# Machnguon.net
KiCad netlist of a schematic drawn in Altium Designer
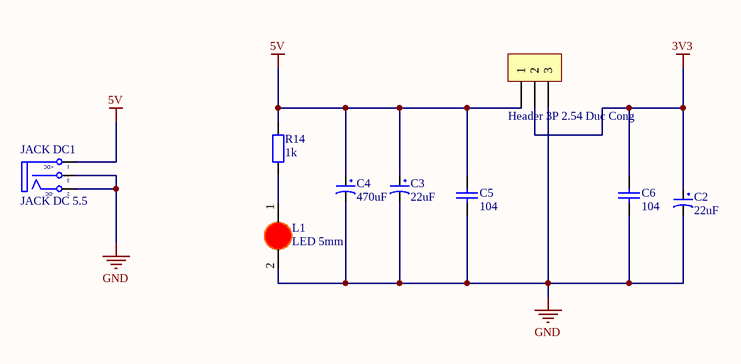
[diagram p0: Machnguon.SchDoc]

(export (version "E")
  (design (tool "Eeschema 10.0.6"))
  (components
    (comp (ref "C2")
      (value "22uF")
      (footprint "tu hoa 5mm")
      (description "Cắm")
      (libsource (lib "Altium_Lib_by_KhueNguyenCreator") (part "Tu Hoa 22uF 35V 5x11"))
    )
    (comp (ref "C3")
      (value "22uF")
      (footprint "tu hoa 5mm")
      (description "Cắm")
      (libsource (lib "Altium_Lib_by_KhueNguyenCreator") (part "Tu Hoa 22uF 35V 5x11"))
    )
    (comp (ref "C4")
      (value "470uF")
      (footprint "tu hoa 8mm")
      (description "Cắm")
      (libsource (lib "Altium_Lib_by_KhueNguyenCreator") (part "Tu Hoa 470uF 16V 8x11"))
    )
    (comp (ref "C5")
      (value "104")
      (footprint "tu gom")
      (description "Cắm")
      (libsource (lib "Altium_Lib_by_KhueNguyenCreator") (part "Tu gom 104 50V"))
    )
    (comp (ref "C6")
      (value "104")
      (footprint "tu gom")
      (description "Cắm")
      (libsource (lib "Altium_Lib_by_KhueNguyenCreator") (part "Tu gom 104 50V"))
    )
    (comp (ref "H14")
      (value "Header 3P 2.54 Duc Cong")
      (footprint "Header 3P DC 2.54")
      (description "Cắm")
      (libsource (lib "Altium_Lib_by_KhueNguyenCreator") (part "Header 3P 2.54 Duc Cong"))
    )
    (comp (ref "JACK DC1")
      (value "JACK DC 5.5")
      (footprint "JACK DC 5.5")
      (libsource (lib "Altium_Lib_by_KhueNguyenCreator") (part "JACK DC 5.5"))
    )
    (comp (ref "L1")
      (value "LED 5mm")
      (footprint "LED-5MM-RED")
      (description "Cắm")
      (libsource (lib "Altium_Lib_by_KhueNguyenCreator") (part "LED 5mm Do"))
    )
    (comp (ref "R14")
      (value "1k")
      (footprint "tro vach 1/4w")
      (description "Cắm")
      (libsource (lib "Altium_Lib_by_KhueNguyenCreator") (part "Tro Vach 1/4W 5% 1k"))
    )
  )
  (nets
    (net (code "1") (name "3V3") (class "Default")
      (node (ref "C2") (pin "1") (pinfunction "1_1") (pintype "passive"))
      (node (ref "C6") (pin "1") (pinfunction "1_1") (pintype "passive"))
      (node (ref "H14") (pin "2") (pinfunction "2_2") (pintype "passive"))
    )
    (net (code "2") (name "5V") (class "Default")
      (node (ref "C3") (pin "1") (pinfunction "1_1") (pintype "passive"))
      (node (ref "C4") (pin "1") (pinfunction "1_1") (pintype "passive"))
      (node (ref "C5") (pin "1") (pinfunction "1_1") (pintype "passive"))
      (node (ref "H14") (pin "1") (pinfunction "1_1") (pintype "passive"))
      (node (ref "JACK DC1") (pin "1") (pinfunction "T_1") (pintype "passive"))
      (node (ref "R14") (pin "2") (pinfunction "2_2") (pintype "passive"))
    )
    (net (code "3") (name "GND") (class "Default")
      (node (ref "C2") (pin "2") (pinfunction "2_2") (pintype "passive"))
      (node (ref "C3") (pin "2") (pinfunction "2_2") (pintype "passive"))
      (node (ref "C4") (pin "2") (pinfunction "2_2") (pintype "passive"))
      (node (ref "C5") (pin "2") (pinfunction "2_2") (pintype "passive"))
      (node (ref "C6") (pin "2") (pinfunction "2_2") (pintype "passive"))
      (node (ref "H14") (pin "3") (pinfunction "3_3") (pintype "passive"))
      (node (ref "JACK DC1") (pin "2") (pinfunction "TN_2") (pintype "passive"))
      (node (ref "JACK DC1") (pin "3") (pinfunction "S_3") (pintype "power_in"))
      (node (ref "L1") (pin "2") (pinfunction "K_2") (pintype "passive"))
    )
    (net (code "4") (name "Net-(L1-A)") (class "Default")
      (node (ref "L1") (pin "1") (pinfunction "A_1") (pintype "passive"))
      (node (ref "R14") (pin "1") (pinfunction "1_1") (pintype "passive"))
    )
  )
)
